# RM-KM-CS.net
KiCad netlist of a schematic drawn in Altium Designer
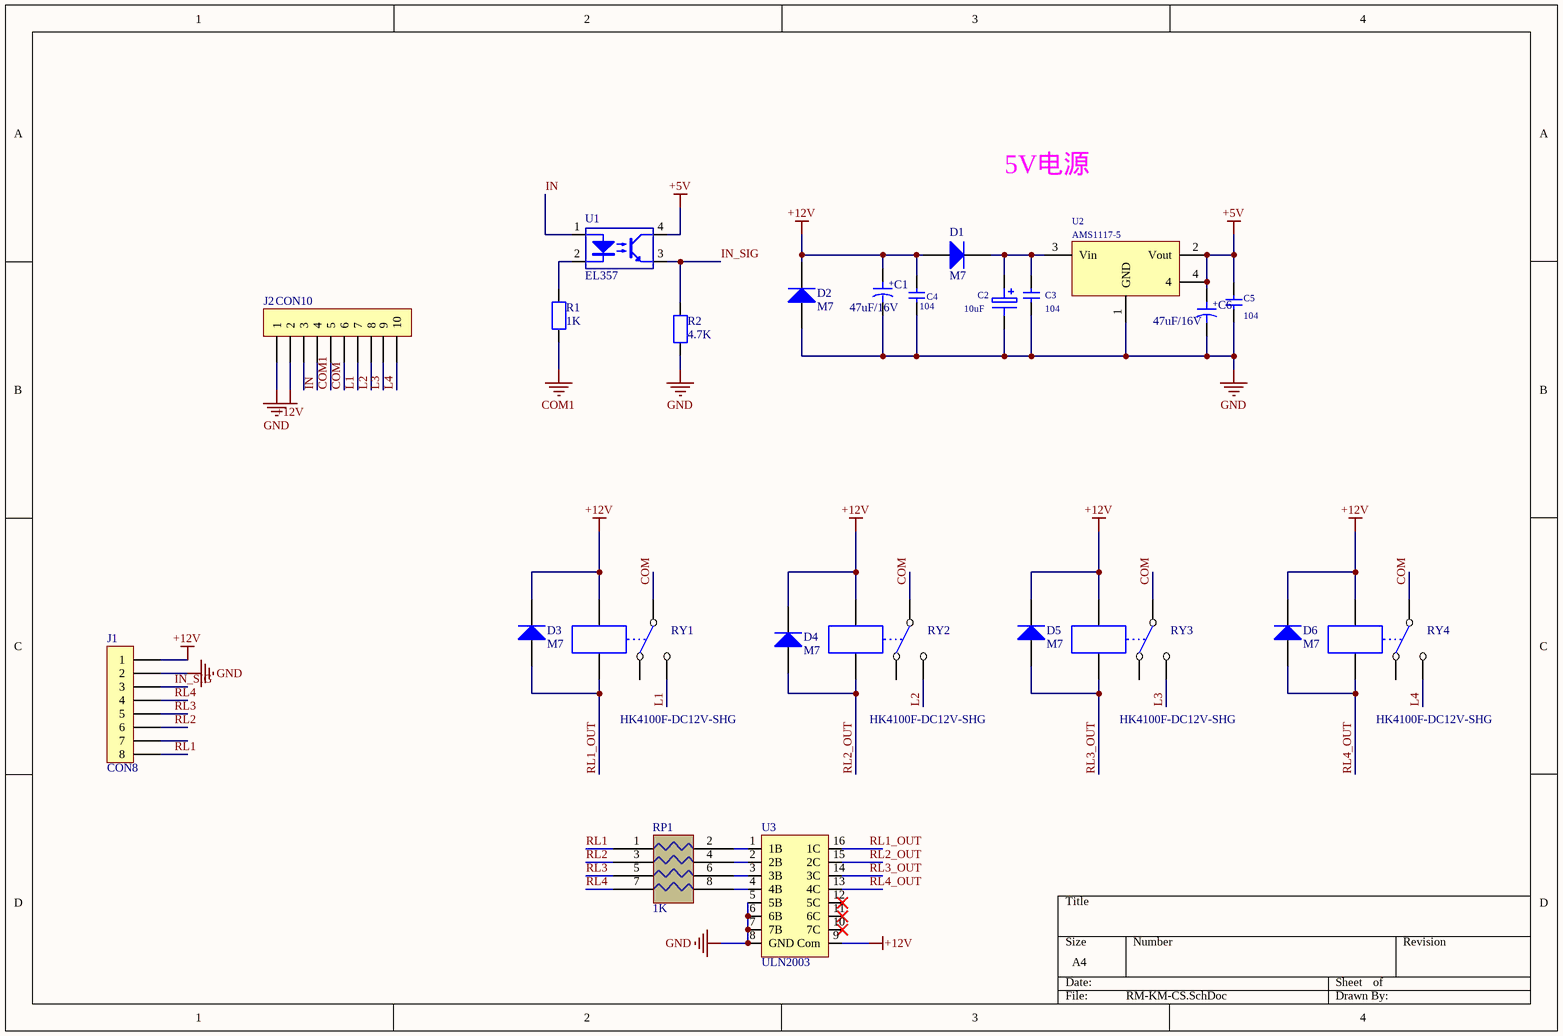
[diagram p0: RM-KM-CS.SchDoc]

(export (version "E")
  (design (tool "Eeschema 10.0.6"))
  (components
    (comp (ref "C1") (value "47uF/16V") (footprint "100uF/16V") (libsource (lib "gsd") (part "ECAP")))
    (comp (ref "C2")
      (value "10uF")
      (footprint "1206C")
      (description "Electrolytic Capacitor")
      (libsource (lib "*") (part "ELECTRO1"))
    )
    (comp (ref "C3") (value "104") (footprint "0805C") (libsource (lib "*") (part "CAP")))
    (comp (ref "C4") (value "104") (footprint "0805C") (libsource (lib "*") (part "CAP")))
    (comp (ref "C5") (value "104") (footprint "0805C") (libsource (lib "*") (part "CAP")))
    (comp (ref "C6") (value "47uF/16V") (footprint "100uF/16V") (libsource (lib "gsd") (part "ECAP")))
    (comp (ref "D1") (value "M7") (footprint "M7") (libsource (lib "gsd") (part "M7")))
    (comp (ref "D2") (value "M7") (footprint "M7") (libsource (lib "gsd") (part "M7")))
    (comp (ref "D3") (value "M7") (footprint "M7") (libsource (lib "gsd") (part "M7")))
    (comp (ref "D4") (value "M7") (footprint "M7") (libsource (lib "gsd") (part "M7")))
    (comp (ref "D5") (value "M7") (footprint "M7") (libsource (lib "gsd") (part "M7")))
    (comp (ref "D6") (value "M7") (footprint "M7") (libsource (lib "gsd") (part "M7")))
    (comp (ref "J1") (value "CON8") (footprint "DIP-8P-2.0 -1") (libsource (lib "gsd") (part "CON8")))
    (comp (ref "J2") (value "CON10") (footprint "SPI-10P-5.0_S") (libsource (lib "gsd") (part "CON10")))
    (comp (ref "R1") (value "1K") (footprint "0805R") (libsource (lib "gsd") (part "RES")))
    (comp (ref "R2") (value "4.7K") (footprint "0805R") (libsource (lib "gsd") (part "RES")))
    (comp (ref "RP1")
      (value "1K")
      (footprint "RP_4P_0603_SMD")
      (description "RP_0603_SMD")
      (libsource (lib "封装") (part "RP-RESISTOR"))
    )
    (comp (ref "RY1")
      (value "HK4100F-DC12V-SHG")
      (footprint "RELAY")
      (libsource (lib "gsd") (part "RELAY5V"))
    )
    (comp (ref "RY2")
      (value "HK4100F-DC12V-SHG")
      (footprint "RELAY")
      (libsource (lib "gsd") (part "RELAY5V"))
    )
    (comp (ref "RY3")
      (value "HK4100F-DC12V-SHG")
      (footprint "RELAY")
      (libsource (lib "gsd") (part "RELAY5V"))
    )
    (comp (ref "RY4")
      (value "HK4100F-DC12V-SHG")
      (footprint "RELAY")
      (libsource (lib "gsd") (part "RELAY5V"))
    )
    (comp (ref "U1") (value "EL357") (footprint "EL357") (libsource (lib "gsd") (part "817")))
    (comp (ref "U2") (value "AMS1117-5") (footprint "SOT-223") (libsource (lib "*") (part "VOL")))
    (comp (ref "U3")
      (value "ULN2003")
      (footprint "SOIC16")
      (description "UNL2003")
      (libsource (lib "封装") (part "UNL2003"))
    )
  )
  (nets
    (net (code "1") (name "+5V") (class "Default")
      (node (ref "C5") (pin "1") (pinfunction "1_1") (pintype "passive"))
      (node (ref "C6") (pin "1") (pinfunction "1_1") (pintype "passive"))
      (node (ref "U1") (pin "4") (pinfunction "Collector_4") (pintype "passive"))
      (node (ref "U2") (pin "2") (pinfunction "Vout_2") (pintype "passive"))
      (node (ref "U2") (pin "4") (pinfunction "4_4") (pintype "passive"))
    )
    (net (code "2") (name "+12V") (class "Default")
      (node (ref "C1") (pin "1") (pinfunction "1_1") (pintype "passive"))
      (node (ref "C4") (pin "1") (pinfunction "1_1") (pintype "passive"))
      (node (ref "D1") (pin "A") (pinfunction "1_A") (pintype "passive"))
      (node (ref "D2") (pin "K") (pinfunction "2_K") (pintype "passive"))
      (node (ref "D3") (pin "K") (pinfunction "2_K") (pintype "passive"))
      (node (ref "D4") (pin "K") (pinfunction "2_K") (pintype "passive"))
      (node (ref "D5") (pin "K") (pinfunction "2_K") (pintype "passive"))
      (node (ref "D6") (pin "K") (pinfunction "2_K") (pintype "passive"))
      (node (ref "J1") (pin "1") (pinfunction "1_1") (pintype "passive"))
      (node (ref "J2") (pin "2") (pinfunction "2_2") (pintype "passive"))
      (node (ref "RY1") (pin "2") (pinfunction "2_2") (pintype "passive"))
      (node (ref "RY2") (pin "2") (pinfunction "2_2") (pintype "passive"))
      (node (ref "RY3") (pin "2") (pinfunction "2_2") (pintype "passive"))
      (node (ref "RY4") (pin "2") (pinfunction "2_2") (pintype "passive"))
      (node (ref "U3") (pin "9") (pinfunction "Com_9") (pintype "passive"))
    )
    (net (code "3") (name "/COM") (class "Default")
      (node (ref "J2") (pin "6") (pinfunction "6_6") (pintype "passive"))
      (node (ref "RY1") (pin "1") (pinfunction "1_1") (pintype "passive"))
      (node (ref "RY2") (pin "1") (pinfunction "1_1") (pintype "passive"))
      (node (ref "RY3") (pin "1") (pinfunction "1_1") (pintype "passive"))
      (node (ref "RY4") (pin "1") (pinfunction "1_1") (pintype "passive"))
    )
    (net (code "4") (name "/IN") (class "Default")
      (node (ref "J2") (pin "4") (pinfunction "4_4") (pintype "passive"))
      (node (ref "U1") (pin "1") (pinfunction "LED_Anode_1") (pintype "passive"))
    )
    (net (code "5") (name "/IN_SIG") (class "Default")
      (node (ref "J1") (pin "3") (pinfunction "3_3") (pintype "passive"))
      (node (ref "R2") (pin "2") (pinfunction "2_2") (pintype "passive"))
      (node (ref "U1") (pin "3") (pinfunction "Emitter_3") (pintype "passive"))
    )
    (net (code "6") (name "/L1") (class "Default")
      (node (ref "J2") (pin "7") (pinfunction "7_7") (pintype "passive"))
      (node (ref "RY1") (pin "4") (pinfunction "4_4") (pintype "passive"))
    )
    (net (code "7") (name "/L2") (class "Default")
      (node (ref "J2") (pin "8") (pinfunction "8_8") (pintype "passive"))
      (node (ref "RY2") (pin "4") (pinfunction "4_4") (pintype "passive"))
    )
    (net (code "8") (name "/L3") (class "Default")
      (node (ref "J2") (pin "9") (pinfunction "9_9") (pintype "passive"))
      (node (ref "RY3") (pin "4") (pinfunction "4_4") (pintype "passive"))
    )
    (net (code "9") (name "/L4") (class "Default")
      (node (ref "J2") (pin "10") (pinfunction "10_10") (pintype "passive"))
      (node (ref "RY4") (pin "4") (pinfunction "4_4") (pintype "passive"))
    )
    (net (code "10") (name "/RL1") (class "Default")
      (node (ref "J1") (pin "8") (pinfunction "8_8") (pintype "passive"))
      (node (ref "RP1") (pin "1") (pinfunction "1_1") (pintype "passive"))
    )
    (net (code "11") (name "/RL1_OUT") (class "Default")
      (node (ref "D3") (pin "A") (pinfunction "1_A") (pintype "passive"))
      (node (ref "RY1") (pin "5") (pinfunction "5_5") (pintype "passive"))
      (node (ref "U3") (pin "16") (pinfunction "1C_16") (pintype "passive"))
    )
    (net (code "12") (name "/RL2") (class "Default")
      (node (ref "J1") (pin "6") (pinfunction "6_6") (pintype "passive"))
      (node (ref "RP1") (pin "3") (pinfunction "3_3") (pintype "passive"))
    )
    (net (code "13") (name "/RL2_OUT") (class "Default")
      (node (ref "D4") (pin "A") (pinfunction "1_A") (pintype "passive"))
      (node (ref "RY2") (pin "5") (pinfunction "5_5") (pintype "passive"))
      (node (ref "U3") (pin "15") (pinfunction "2C_15") (pintype "passive"))
    )
    (net (code "14") (name "/RL3") (class "Default")
      (node (ref "J1") (pin "5") (pinfunction "5_5") (pintype "passive"))
      (node (ref "RP1") (pin "5") (pinfunction "5_5") (pintype "passive"))
    )
    (net (code "15") (name "/RL3_OUT") (class "Default")
      (node (ref "D5") (pin "A") (pinfunction "1_A") (pintype "passive"))
      (node (ref "RY3") (pin "5") (pinfunction "5_5") (pintype "passive"))
      (node (ref "U3") (pin "14") (pinfunction "3C_14") (pintype "passive"))
    )
    (net (code "16") (name "/RL4") (class "Default")
      (node (ref "J1") (pin "4") (pinfunction "4_4") (pintype "passive"))
      (node (ref "RP1") (pin "7") (pinfunction "7_7") (pintype "passive"))
    )
    (net (code "17") (name "/RL4_OUT") (class "Default")
      (node (ref "D6") (pin "A") (pinfunction "1_A") (pintype "passive"))
      (node (ref "RY4") (pin "5") (pinfunction "5_5") (pintype "passive"))
      (node (ref "U3") (pin "13") (pinfunction "4C_13") (pintype "passive"))
    )
    (net (code "18") (name "COM1") (class "Default")
      (node (ref "J2") (pin "5") (pinfunction "5_5") (pintype "passive"))
      (node (ref "R1") (pin "1") (pinfunction "1_1") (pintype "passive"))
    )
    (net (code "19") (name "GND") (class "Default")
      (node (ref "C1") (pin "2") (pinfunction "2_2") (pintype "passive"))
      (node (ref "C2") (pin "2") (pinfunction "2_2") (pintype "passive"))
      (node (ref "C3") (pin "2") (pinfunction "2_2") (pintype "passive"))
      (node (ref "C4") (pin "2") (pinfunction "2_2") (pintype "passive"))
      (node (ref "C5") (pin "2") (pinfunction "2_2") (pintype "passive"))
      (node (ref "C6") (pin "2") (pinfunction "2_2") (pintype "passive"))
      (node (ref "D2") (pin "A") (pinfunction "1_A") (pintype "passive"))
      (node (ref "J1") (pin "2") (pinfunction "2_2") (pintype "passive"))
      (node (ref "J2") (pin "1") (pinfunction "1_1") (pintype "passive"))
      (node (ref "R2") (pin "1") (pinfunction "1_1") (pintype "passive"))
      (node (ref "U2") (pin "1") (pinfunction "GND_1") (pintype "passive"))
      (node (ref "U3") (pin "5") (pinfunction "5B_5") (pintype "passive"))
      (node (ref "U3") (pin "6") (pinfunction "6B_6") (pintype "passive"))
      (node (ref "U3") (pin "7") (pinfunction "7B_7") (pintype "passive"))
      (node (ref "U3") (pin "8") (pinfunction "GND_8") (pintype "passive"))
    )
    (net (code "20") (name "Net-(D1-2)") (class "Default")
      (node (ref "C2") (pin "1") (pinfunction "1_1") (pintype "passive"))
      (node (ref "C3") (pin "1") (pinfunction "1_1") (pintype "passive"))
      (node (ref "D1") (pin "K") (pinfunction "2_K") (pintype "passive"))
      (node (ref "U2") (pin "3") (pinfunction "Vin_3") (pintype "passive"))
    )
    (net (code "21") (name "Net-(U1-LED_Cathode)") (class "Default")
      (node (ref "R1") (pin "2") (pinfunction "2_2") (pintype "passive"))
      (node (ref "U1") (pin "2") (pinfunction "LED_Cathode_2") (pintype "passive"))
    )
    (net (code "22") (name "Net-(U3-1B)") (class "Default")
      (node (ref "RP1") (pin "2") (pinfunction "2_2") (pintype "passive"))
      (node (ref "U3") (pin "1") (pinfunction "1B_1") (pintype "passive"))
    )
    (net (code "23") (name "Net-(U3-2B)") (class "Default")
      (node (ref "RP1") (pin "4") (pinfunction "4_4") (pintype "passive"))
      (node (ref "U3") (pin "2") (pinfunction "2B_2") (pintype "passive"))
    )
    (net (code "24") (name "Net-(U3-3B)") (class "Default")
      (node (ref "RP1") (pin "6") (pinfunction "6_6") (pintype "passive"))
      (node (ref "U3") (pin "3") (pinfunction "3B_3") (pintype "passive"))
    )
    (net (code "25") (name "Net-(U3-4B)") (class "Default")
      (node (ref "RP1") (pin "8") (pinfunction "8_8") (pintype "passive"))
      (node (ref "U3") (pin "4") (pinfunction "4B_4") (pintype "passive"))
    )
    (net (code "26") (name "unconnected-(J1-Pad7)") (class "Default")
      (node (ref "J1") (pin "7") (pinfunction "7_7") (pintype "passive"))
    )
    (net (code "27") (name "unconnected-(J2-Pad3)") (class "Default")
      (node (ref "J2") (pin "3") (pinfunction "3_3") (pintype "passive"))
    )
    (net (code "28") (name "unconnected-(RY1-Pad3)") (class "Default")
      (node (ref "RY1") (pin "3") (pinfunction "3_3") (pintype "passive"))
    )
    (net (code "29") (name "unconnected-(RY2-Pad3)") (class "Default")
      (node (ref "RY2") (pin "3") (pinfunction "3_3") (pintype "passive"))
    )
    (net (code "30") (name "unconnected-(RY3-Pad3)") (class "Default")
      (node (ref "RY3") (pin "3") (pinfunction "3_3") (pintype "passive"))
    )
    (net (code "31") (name "unconnected-(RY4-Pad3)") (class "Default")
      (node (ref "RY4") (pin "3") (pinfunction "3_3") (pintype "passive"))
    )
    (net (code "32") (name "unconnected-(U3-5C-Pad12)") (class "Default")
      (node (ref "U3") (pin "12") (pinfunction "5C_12") (pintype "passive+no_connect"))
    )
    (net (code "33") (name "unconnected-(U3-6C-Pad11)") (class "Default")
      (node (ref "U3") (pin "11") (pinfunction "6C_11") (pintype "passive+no_connect"))
    )
    (net (code "34") (name "unconnected-(U3-7C-Pad10)") (class "Default")
      (node (ref "U3") (pin "10") (pinfunction "7C_10") (pintype "passive+no_connect"))
    )
  )
)
